# pcb-exp-ctrl.net
KiCad netlist of a schematic drawn in EAGLE
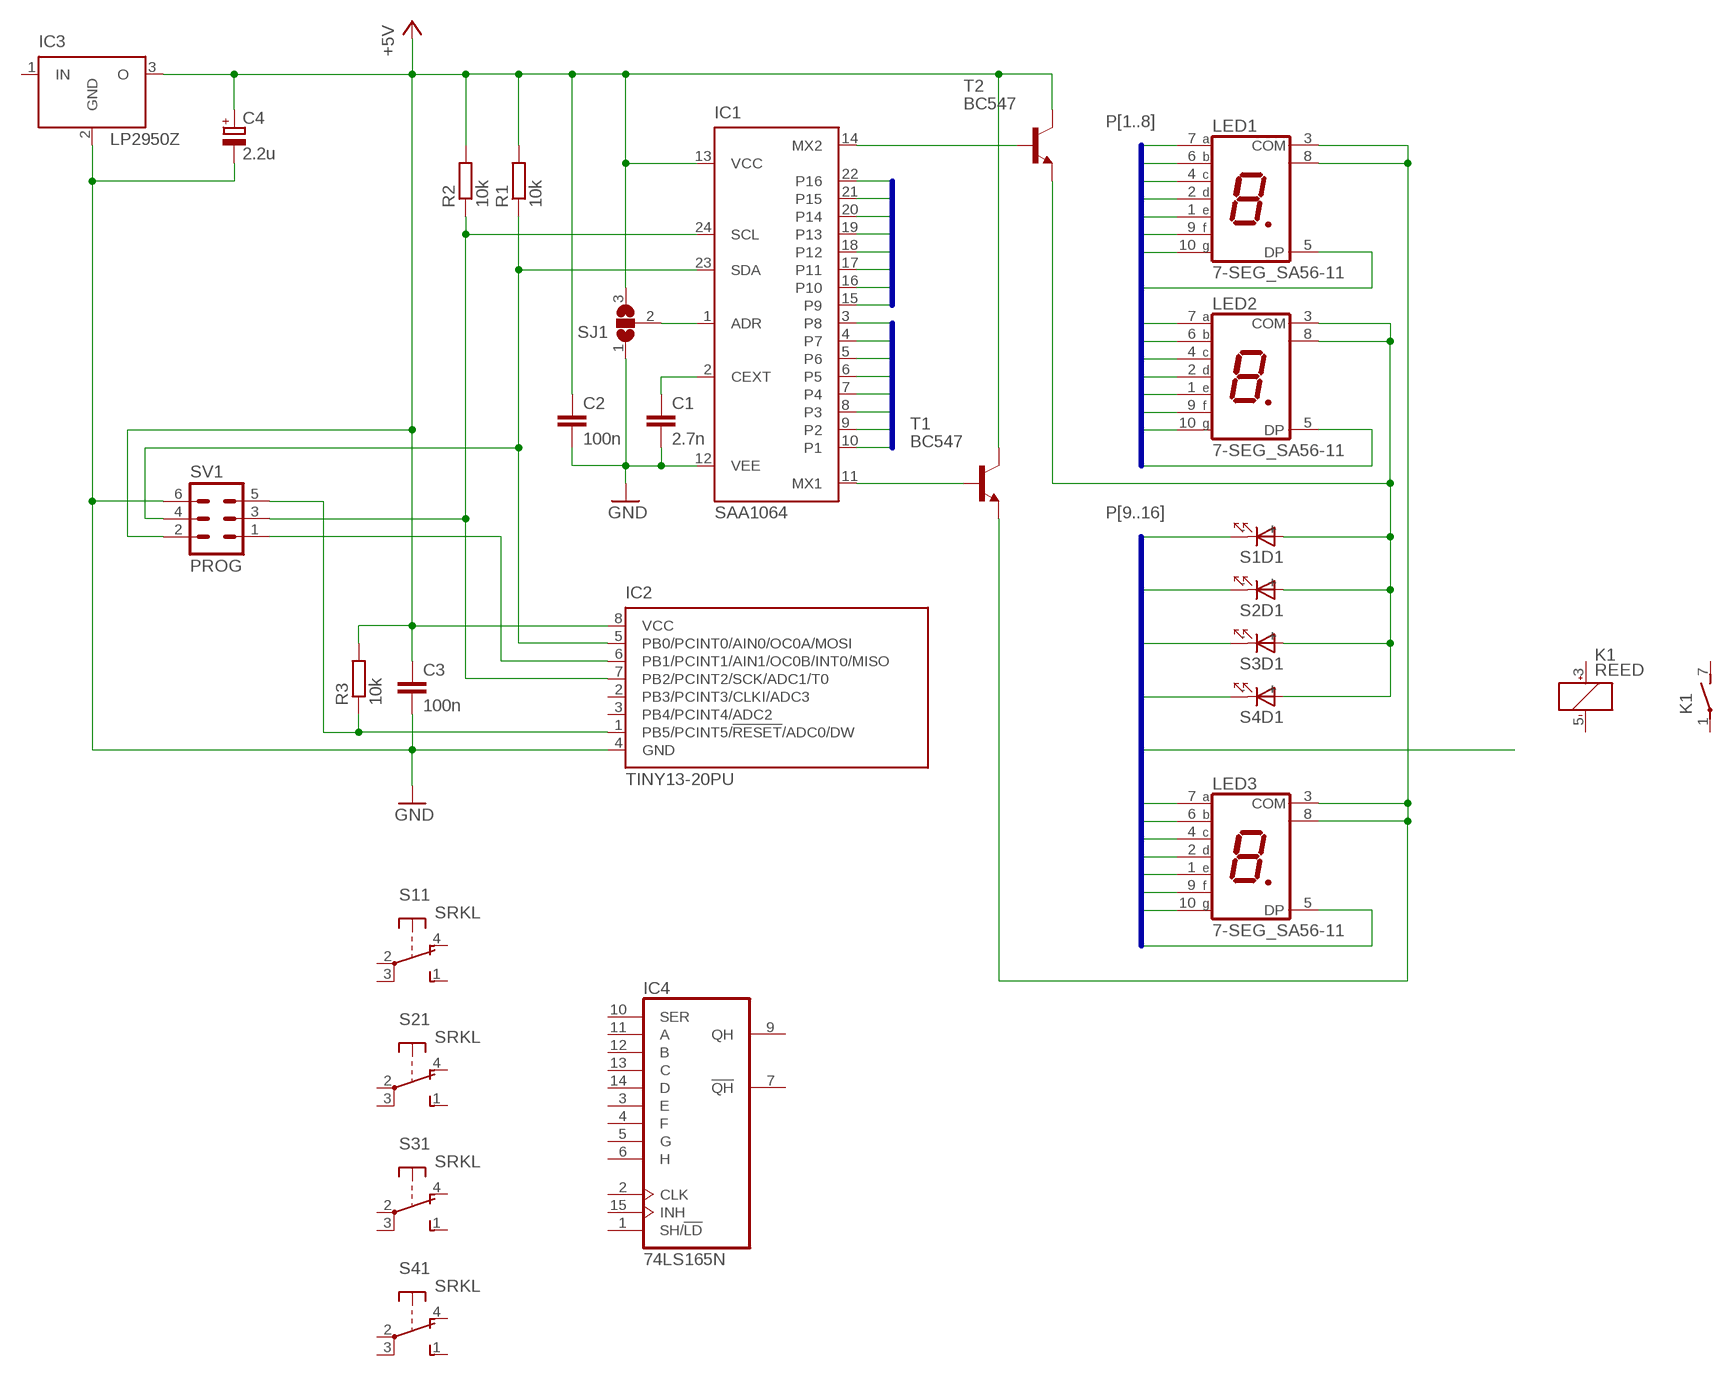
[diagram p0: schematic, sheet 1]

(export (version "E")
  (design (tool "Eeschema 10.0.6"))
  (components
    (comp (ref "C1")
      (value "2.7n")
      (footprint "eagle-import:C025-025X050")
      (libsource (lib "eagle-import") (part "C-EU025-025X050"))
    )
    (comp (ref "C2")
      (value "100n")
      (footprint "eagle-import:C025-025X050")
      (libsource (lib "eagle-import") (part "C-EU025-025X050"))
    )
    (comp (ref "C3")
      (value "100n")
      (footprint "eagle-import:C025-025X050")
      (libsource (lib "eagle-import") (part "C-EU025-025X050"))
    )
    (comp (ref "C4")
      (value "2.2u")
      (footprint "eagle-import:E2,5-6")
      (libsource (lib "eagle-import") (part "CPOL-EUE2.5-6"))
    )
    (comp (ref "IC1")
      (value "SAA1064")
      (footprint "eagle-import:DIL24-6")
      (fields (field (name "MPN") "SAA1064/N2,112"))
      (libsource (lib "eagle-import") (part "SAA1064"))
    )
    (comp (ref "IC2")
      (value "TINY13-20PU")
      (footprint "eagle-import:DIL08")
      (fields (field (name "MPN") "ATTINY13-20PU"))
      (libsource (lib "eagle-import") (part "TINY13PU-20"))
    )
    (comp (ref "IC3")
      (value "LP2950Z")
      (footprint "eagle-import:TO92")
      (fields (field (name "MF") "NATIONAL SEMICONDUCTOR") (field (name "MPN") "LP2950CZ-5.0/NOPB"))
      (libsource (lib "eagle-import") (part "LP2950Z"))
    )
    (comp (ref "IC4")
      (value "74LS165N")
      (footprint "eagle-import:DIL16")
      (libsource (lib "eagle-import") (part "74165NLS"))
    )
    (comp (ref "K1")
      (value "REED")
      (footprint "eagle-import:REED")
      (libsource (lib "eagle-import") (part "REED"))
    )
    (comp (ref "LED1")
      (value "7-SEG_SA56-11")
      (footprint "eagle-import:SA56-11")
      (libsource (lib "eagle-import") (part "7-SEG_SA56-11"))
    )
    (comp (ref "LED2")
      (value "7-SEG_SA56-11")
      (footprint "eagle-import:SA56-11")
      (libsource (lib "eagle-import") (part "7-SEG_SA56-11"))
    )
    (comp (ref "LED3")
      (value "7-SEG_SA56-11")
      (footprint "eagle-import:SA56-11")
      (libsource (lib "eagle-import") (part "7-SEG_SA56-11"))
    )
    (comp (ref "R1")
      (value "10k")
      (footprint "eagle-import:0204_7")
      (libsource (lib "eagle-import") (part "R-EU_0204/7"))
    )
    (comp (ref "R2")
      (value "10k")
      (footprint "eagle-import:0204_7")
      (libsource (lib "eagle-import") (part "R-EU_0204/7"))
    )
    (comp (ref "R3")
      (value "10k")
      (footprint "eagle-import:0204_7")
      (libsource (lib "eagle-import") (part "R-EU_0204/7"))
    )
    (comp (ref "S1")
      (value "SRKL")
      (footprint "eagle-import:SRKL")
      (libsource (lib "eagle-import") (part "SRKL"))
    )
    (comp (ref "S2")
      (value "SRKL")
      (footprint "eagle-import:SRKL")
      (libsource (lib "eagle-import") (part "SRKL"))
    )
    (comp (ref "S3")
      (value "SRKL")
      (footprint "eagle-import:SRKL")
      (libsource (lib "eagle-import") (part "SRKL"))
    )
    (comp (ref "S4")
      (value "SRKL")
      (footprint "eagle-import:SRKL")
      (libsource (lib "eagle-import") (part "SRKL"))
    )
    (comp (ref "SJ1")
      (value "SJ2W")
      (footprint "eagle-import:SJ_2")
      (libsource (lib "eagle-import") (part "SJ2W"))
    )
    (comp (ref "SV1")
      (value "PROG")
      (footprint "eagle-import:ML6")
      (libsource (lib "eagle-import") (part "ML6"))
    )
    (comp (ref "T1")
      (value "BC547")
      (footprint "eagle-import:TO92")
      (libsource (lib "eagle-import") (part "BC547"))
    )
    (comp (ref "T2")
      (value "BC547")
      (footprint "eagle-import:TO92")
      (libsource (lib "eagle-import") (part "BC547"))
    )
  )
  (nets
    (net (code "1") (name "+5V") (class "Default")
      (node (ref "C2") (pin "1") (pinfunction "1_1") (pintype "passive"))
      (node (ref "C3") (pin "1") (pinfunction "1_1") (pintype "passive"))
      (node (ref "C4") (pin "+") (pinfunction "+_+") (pintype "passive"))
      (node (ref "IC1") (pin "13") (pinfunction "VCC_13") (pintype "power_in"))
      (node (ref "IC2") (pin "8") (pinfunction "VCC_8") (pintype "power_in"))
      (node (ref "IC3") (pin "3") (pinfunction "O_3") (pintype "output"))
      (node (ref "R1") (pin "2") (pinfunction "2_2") (pintype "passive"))
      (node (ref "R2") (pin "2") (pinfunction "2_2") (pintype "passive"))
      (node (ref "R3") (pin "2") (pinfunction "2_2") (pintype "passive"))
      (node (ref "SJ1") (pin "3") (pinfunction "3_3") (pintype "passive"))
      (node (ref "SV1") (pin "2") (pinfunction "2_2") (pintype "passive"))
      (node (ref "T1") (pin "3") (pinfunction "C_3") (pintype "passive"))
      (node (ref "T2") (pin "3") (pinfunction "C_3") (pintype "passive"))
    )
    (net (code "4") (name "GND") (class "Default")
      (node (ref "C1") (pin "2") (pinfunction "2_2") (pintype "passive"))
      (node (ref "C2") (pin "2") (pinfunction "2_2") (pintype "passive"))
      (node (ref "C3") (pin "2") (pinfunction "2_2") (pintype "passive"))
      (node (ref "C4") (pin "-") (pinfunction "-_-") (pintype "passive"))
      (node (ref "IC1") (pin "12") (pinfunction "VEE_12") (pintype "power_in"))
      (node (ref "IC2") (pin "4") (pinfunction "GND_4") (pintype "power_in"))
      (node (ref "IC3") (pin "2") (pinfunction "GND_2") (pintype "power_in"))
      (node (ref "SJ1") (pin "1") (pinfunction "1_1") (pintype "passive"))
      (node (ref "SV1") (pin "6") (pinfunction "6_6") (pintype "passive"))
    )
    (net (code "5") (name "Net-(IC1-ADR)") (class "Default")
      (node (ref "IC1") (pin "1") (pinfunction "ADR_1") (pintype "input"))
      (node (ref "SJ1") (pin "2") (pinfunction "2_2") (pintype "passive"))
    )
    (net (code "6") (name "Net-(IC1-CEXT)") (class "Default")
      (node (ref "C1") (pin "1") (pinfunction "1_1") (pintype "passive"))
      (node (ref "IC1") (pin "2") (pinfunction "CEXT_2") (pintype "input"))
    )
    (net (code "7") (name "Net-(IC1-MX1)") (class "Default")
      (node (ref "IC1") (pin "11") (pinfunction "MX1_11") (pintype "output"))
      (node (ref "T1") (pin "2") (pinfunction "B_2") (pintype "passive"))
    )
    (net (code "8") (name "Net-(IC1-MX2)") (class "Default")
      (node (ref "IC1") (pin "14") (pinfunction "MX2_14") (pintype "output"))
      (node (ref "T2") (pin "2") (pinfunction "B_2") (pintype "passive"))
    )
    (net (code "9") (name "Net-(IC1-SCL)") (class "Default")
      (node (ref "IC1") (pin "24") (pinfunction "SCL_24") (pintype "input"))
      (node (ref "IC2") (pin "7") (pinfunction "PB2/PCINT2/SCK/ADC1/T0_7") (pintype "bidirectional"))
      (node (ref "R2") (pin "1") (pinfunction "1_1") (pintype "passive"))
      (node (ref "SV1") (pin "3") (pinfunction "3_3") (pintype "passive"))
    )
    (net (code "10") (name "Net-(IC1-SDA)") (class "Default")
      (node (ref "IC1") (pin "23") (pinfunction "SDA_23") (pintype "input"))
      (node (ref "IC2") (pin "5") (pinfunction "PB0/PCINT0/AIN0/OC0A/MOSI_5") (pintype "bidirectional"))
      (node (ref "R1") (pin "1") (pinfunction "1_1") (pintype "passive"))
      (node (ref "SV1") (pin "4") (pinfunction "4_4") (pintype "passive"))
    )
    (net (code "11") (name "Net-(IC2-PB1{slash}PCINT1{slash}AIN1{slash}OC0B{slash}INT0{slash}MISO)") (class "Default")
      (node (ref "IC2") (pin "6") (pinfunction "PB1/PCINT1/AIN1/OC0B/INT0/MISO_6") (pintype "bidirectional"))
      (node (ref "SV1") (pin "1") (pinfunction "1_1") (pintype "passive"))
    )
    (net (code "12") (name "Net-(IC2-PB5{slash}PCINT5{slash}~{RESET}{slash}ADC0{slash}DW)") (class "Default")
      (node (ref "IC2") (pin "1") (pinfunction "PB5/PCINT5/~{RESET}/ADC0/DW_1") (pintype "bidirectional"))
      (node (ref "R3") (pin "1") (pinfunction "1_1") (pintype "passive"))
      (node (ref "SV1") (pin "5") (pinfunction "5_5") (pintype "passive"))
    )
    (net (code "13") (name "Net-(S1B-A)") (class "Default")
      (node (ref "LED2") (pin "3") (pinfunction "COM_3") (pintype "passive"))
      (node (ref "LED2") (pin "8") (pinfunction "COM_8") (pintype "passive"))
      (node (ref "S1") (pin "+") (pinfunction "A_+") (pintype "passive"))
      (node (ref "S2") (pin "+") (pinfunction "A_+") (pintype "passive"))
      (node (ref "S3") (pin "+") (pinfunction "A_+") (pintype "passive"))
      (node (ref "S4") (pin "+") (pinfunction "A_+") (pintype "passive"))
      (node (ref "T2") (pin "1") (pinfunction "E_1") (pintype "passive"))
    )
    (net (code "14") (name "Net-(T1-E)") (class "Default")
      (node (ref "LED1") (pin "3") (pinfunction "COM_3") (pintype "passive"))
      (node (ref "LED1") (pin "8") (pinfunction "COM_8") (pintype "passive"))
      (node (ref "LED3") (pin "3") (pinfunction "COM_3") (pintype "passive"))
      (node (ref "LED3") (pin "8") (pinfunction "COM_8") (pintype "passive"))
      (node (ref "T1") (pin "1") (pinfunction "E_1") (pintype "passive"))
    )
    (net (code "15") (name "P1") (class "Default")
      (node (ref "IC1") (pin "10") (pinfunction "P1_10") (pintype "output"))
      (node (ref "LED1") (pin "7") (pinfunction "A_7") (pintype "passive"))
      (node (ref "LED2") (pin "7") (pinfunction "A_7") (pintype "passive"))
    )
    (net (code "16") (name "P2") (class "Default")
      (node (ref "IC1") (pin "9") (pinfunction "P2_9") (pintype "output"))
      (node (ref "LED1") (pin "6") (pinfunction "B_6") (pintype "passive"))
      (node (ref "LED2") (pin "6") (pinfunction "B_6") (pintype "passive"))
    )
    (net (code "17") (name "P3") (class "Default")
      (node (ref "IC1") (pin "8") (pinfunction "P3_8") (pintype "output"))
      (node (ref "LED1") (pin "4") (pinfunction "C_4") (pintype "passive"))
      (node (ref "LED2") (pin "4") (pinfunction "C_4") (pintype "passive"))
    )
    (net (code "18") (name "P4") (class "Default")
      (node (ref "IC1") (pin "7") (pinfunction "P4_7") (pintype "output"))
      (node (ref "LED1") (pin "2") (pinfunction "D_2") (pintype "passive"))
      (node (ref "LED2") (pin "2") (pinfunction "D_2") (pintype "passive"))
    )
    (net (code "19") (name "P5") (class "Default")
      (node (ref "IC1") (pin "6") (pinfunction "P5_6") (pintype "output"))
      (node (ref "LED1") (pin "1") (pinfunction "E_1") (pintype "passive"))
      (node (ref "LED2") (pin "1") (pinfunction "E_1") (pintype "passive"))
    )
    (net (code "20") (name "P6") (class "Default")
      (node (ref "IC1") (pin "5") (pinfunction "P6_5") (pintype "output"))
      (node (ref "LED1") (pin "9") (pinfunction "F_9") (pintype "passive"))
      (node (ref "LED2") (pin "9") (pinfunction "F_9") (pintype "passive"))
    )
    (net (code "21") (name "P7") (class "Default")
      (node (ref "IC1") (pin "4") (pinfunction "P7_4") (pintype "output"))
      (node (ref "LED1") (pin "10") (pinfunction "G_10") (pintype "passive"))
      (node (ref "LED2") (pin "10") (pinfunction "G_10") (pintype "passive"))
    )
    (net (code "22") (name "P8") (class "Default")
      (node (ref "IC1") (pin "3") (pinfunction "P8_3") (pintype "output"))
      (node (ref "LED1") (pin "5") (pinfunction "DP_5") (pintype "passive"))
      (node (ref "LED2") (pin "5") (pinfunction "DP_5") (pintype "passive"))
    )
    (net (code "23") (name "P9") (class "Default")
      (node (ref "IC1") (pin "15") (pinfunction "P9_15") (pintype "output"))
      (node (ref "LED3") (pin "7") (pinfunction "A_7") (pintype "passive"))
      (node (ref "S1") (pin "-") (pinfunction "C_-") (pintype "passive"))
    )
    (net (code "24") (name "P10") (class "Default")
      (node (ref "IC1") (pin "16") (pinfunction "P10_16") (pintype "output"))
      (node (ref "LED3") (pin "6") (pinfunction "B_6") (pintype "passive"))
      (node (ref "S2") (pin "-") (pinfunction "C_-") (pintype "passive"))
    )
    (net (code "25") (name "P11") (class "Default")
      (node (ref "IC1") (pin "17") (pinfunction "P11_17") (pintype "output"))
      (node (ref "LED3") (pin "4") (pinfunction "C_4") (pintype "passive"))
      (node (ref "S3") (pin "-") (pinfunction "C_-") (pintype "passive"))
    )
    (net (code "26") (name "P12") (class "Default")
      (node (ref "IC1") (pin "18") (pinfunction "P12_18") (pintype "output"))
      (node (ref "LED3") (pin "2") (pinfunction "D_2") (pintype "passive"))
      (node (ref "S4") (pin "-") (pinfunction "C_-") (pintype "passive"))
    )
    (net (code "27") (name "P13") (class "Default")
      (node (ref "IC1") (pin "19") (pinfunction "P13_19") (pintype "output"))
      (node (ref "LED3") (pin "1") (pinfunction "E_1") (pintype "passive"))
    )
    (net (code "28") (name "P14") (class "Default")
      (node (ref "IC1") (pin "20") (pinfunction "P14_20") (pintype "output"))
      (node (ref "LED3") (pin "9") (pinfunction "F_9") (pintype "passive"))
    )
    (net (code "29") (name "P15") (class "Default")
      (node (ref "IC1") (pin "21") (pinfunction "P15_21") (pintype "output"))
      (node (ref "LED3") (pin "10") (pinfunction "G_10") (pintype "passive"))
    )
    (net (code "30") (name "P16") (class "Default")
      (node (ref "IC1") (pin "22") (pinfunction "P16_22") (pintype "output"))
      (node (ref "LED3") (pin "5") (pinfunction "DP_5") (pintype "passive"))
    )
    (net (code "31") (name "unconnected-(IC2-PB3{slash}PCINT3{slash}CLKI{slash}ADC3-Pad2)") (class "Default")
      (node (ref "IC2") (pin "2") (pinfunction "PB3/PCINT3/CLKI/ADC3_2") (pintype "bidirectional"))
    )
    (net (code "32") (name "unconnected-(IC2-PB4{slash}PCINT4{slash}ADC2-Pad3)") (class "Default")
      (node (ref "IC2") (pin "3") (pinfunction "PB4/PCINT4/ADC2_3") (pintype "bidirectional"))
    )
    (net (code "33") (name "unconnected-(IC3-IN-Pad1)") (class "Default")
      (node (ref "IC3") (pin "1") (pinfunction "IN_1") (pintype "input"))
    )
    (net (code "34") (name "unconnected-(IC4A-A-Pad11)") (class "Default")
      (node (ref "IC4") (pin "11") (pinfunction "A_11") (pintype "input"))
    )
    (net (code "35") (name "unconnected-(IC4A-B-Pad12)") (class "Default")
      (node (ref "IC4") (pin "12") (pinfunction "B_12") (pintype "input"))
    )
    (net (code "36") (name "unconnected-(IC4A-C-Pad13)") (class "Default")
      (node (ref "IC4") (pin "13") (pinfunction "C_13") (pintype "input"))
    )
    (net (code "37") (name "unconnected-(IC4A-CLK-Pad2)") (class "Default")
      (node (ref "IC4") (pin "2") (pinfunction "CLK_2") (pintype "input"))
    )
    (net (code "38") (name "unconnected-(IC4A-D-Pad14)") (class "Default")
      (node (ref "IC4") (pin "14") (pinfunction "D_14") (pintype "input"))
    )
    (net (code "39") (name "unconnected-(IC4A-E-Pad3)") (class "Default")
      (node (ref "IC4") (pin "3") (pinfunction "E_3") (pintype "input"))
    )
    (net (code "40") (name "unconnected-(IC4A-F-Pad4)") (class "Default")
      (node (ref "IC4") (pin "4") (pinfunction "F_4") (pintype "input"))
    )
    (net (code "41") (name "unconnected-(IC4A-G-Pad5)") (class "Default")
      (node (ref "IC4") (pin "5") (pinfunction "G_5") (pintype "input"))
    )
    (net (code "42") (name "unconnected-(IC4A-H-Pad6)") (class "Default")
      (node (ref "IC4") (pin "6") (pinfunction "H_6") (pintype "input"))
    )
    (net (code "43") (name "unconnected-(IC4A-INH-Pad15)") (class "Default")
      (node (ref "IC4") (pin "15") (pinfunction "INH_15") (pintype "input"))
    )
    (net (code "44") (name "unconnected-(IC4A-QH-Pad9)") (class "Default")
      (node (ref "IC4") (pin "9") (pinfunction "QH_9") (pintype "output"))
    )
    (net (code "45") (name "unconnected-(IC4A-SER-Pad10)") (class "Default")
      (node (ref "IC4") (pin "10") (pinfunction "SER_10") (pintype "input"))
    )
    (net (code "46") (name "unconnected-(IC4A-SH{slash}~{LD}-Pad1)") (class "Default")
      (node (ref "IC4") (pin "1") (pinfunction "SH/~{LD}_1") (pintype "input"))
    )
    (net (code "47") (name "unconnected-(IC4A-~{QH}-Pad7)") (class "Default")
      (node (ref "IC4") (pin "7") (pinfunction "~{QH}_7") (pintype "output"))
    )
    (net (code "48") (name "unconnected-(K1A-+-Pad3)") (class "Default")
      (node (ref "K1") (pin "3") (pinfunction "+_3") (pintype "passive"))
    )
    (net (code "49") (name "unconnected-(K1A---Pad5)") (class "Default")
      (node (ref "K1") (pin "5") (pinfunction "-_5") (pintype "passive"))
    )
    (net (code "50") (name "unconnected-(K1B-P-Pad1)") (class "Default")
      (node (ref "K1") (pin "1") (pinfunction "P_1") (pintype "passive"))
    )
    (net (code "51") (name "unconnected-(K1B-S-Pad7)") (class "Default")
      (node (ref "K1") (pin "7") (pinfunction "S_7") (pintype "passive"))
    )
    (net (code "52") (name "unconnected-(S1A-O-Pad4)") (class "Default")
      (node (ref "S1") (pin "4") (pinfunction "O_4") (pintype "passive"))
    )
    (net (code "53") (name "unconnected-(S1A-P-Pad2)") (class "Default")
      (node (ref "S1") (pin "2") (pinfunction "P_2") (pintype "passive"))
    )
    (net (code "54") (name "unconnected-(S1A-P-Pad3)") (class "Default")
      (node (ref "S1") (pin "3") (pinfunction "P_3") (pintype "passive"))
    )
    (net (code "55") (name "unconnected-(S1A-S-Pad1)") (class "Default")
      (node (ref "S1") (pin "1") (pinfunction "S_1") (pintype "passive"))
    )
    (net (code "56") (name "unconnected-(S2A-O-Pad4)") (class "Default")
      (node (ref "S2") (pin "4") (pinfunction "O_4") (pintype "passive"))
    )
    (net (code "57") (name "unconnected-(S2A-P-Pad2)") (class "Default")
      (node (ref "S2") (pin "2") (pinfunction "P_2") (pintype "passive"))
    )
    (net (code "58") (name "unconnected-(S2A-P-Pad3)") (class "Default")
      (node (ref "S2") (pin "3") (pinfunction "P_3") (pintype "passive"))
    )
    (net (code "59") (name "unconnected-(S2A-S-Pad1)") (class "Default")
      (node (ref "S2") (pin "1") (pinfunction "S_1") (pintype "passive"))
    )
    (net (code "60") (name "unconnected-(S3A-O-Pad4)") (class "Default")
      (node (ref "S3") (pin "4") (pinfunction "O_4") (pintype "passive"))
    )
    (net (code "61") (name "unconnected-(S3A-P-Pad2)") (class "Default")
      (node (ref "S3") (pin "2") (pinfunction "P_2") (pintype "passive"))
    )
    (net (code "62") (name "unconnected-(S3A-P-Pad3)") (class "Default")
      (node (ref "S3") (pin "3") (pinfunction "P_3") (pintype "passive"))
    )
    (net (code "63") (name "unconnected-(S3A-S-Pad1)") (class "Default")
      (node (ref "S3") (pin "1") (pinfunction "S_1") (pintype "passive"))
    )
    (net (code "64") (name "unconnected-(S4A-O-Pad4)") (class "Default")
      (node (ref "S4") (pin "4") (pinfunction "O_4") (pintype "passive"))
    )
    (net (code "65") (name "unconnected-(S4A-P-Pad2)") (class "Default")
      (node (ref "S4") (pin "2") (pinfunction "P_2") (pintype "passive"))
    )
    (net (code "66") (name "unconnected-(S4A-P-Pad3)") (class "Default")
      (node (ref "S4") (pin "3") (pinfunction "P_3") (pintype "passive"))
    )
    (net (code "67") (name "unconnected-(S4A-S-Pad1)") (class "Default")
      (node (ref "S4") (pin "1") (pinfunction "S_1") (pintype "passive"))
    )
  )
)
